# rs485Adaptor.net
KiCad netlist of a schematic drawn in EAGLE
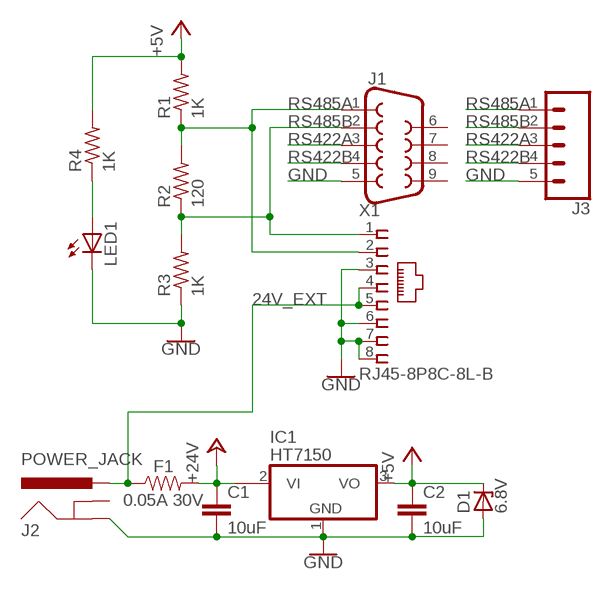
[diagram p0: schematic, sheet 1]

(export (version "E")
  (design (tool "Eeschema 10.0.6"))
  (components
    (comp (ref "C1")
      (value "10uF")
      (footprint "eagle-import:1206")
      (libsource (lib "eagle-import") (part "10UF-1206-6.3V-20%"))
    )
    (comp (ref "C2")
      (value "10uF")
      (footprint "eagle-import:C0805K")
      (libsource (lib "eagle-import") (part "C-EUC0805K"))
    )
    (comp (ref "D1")
      (value "6.8V")
      (footprint "eagle-import:SOD80C")
      (libsource (lib "eagle-import") (part "ZENER-DIODESOD80C"))
    )
    (comp (ref "F1")
      (value "0.05A 30V")
      (footprint "eagle-import:1210")
      (libsource (lib "eagle-import") (part "0.1OHM-1210-1/2W-1%"))
    )
    (comp (ref "IC1")
      (value "HT7150")
      (footprint "eagle-import:SOT89")
      (libsource (lib "eagle-import") (part "MCP1703MB50"))
    )
    (comp (ref "J1")
      (value "DB9FEMALE")
      (footprint "eagle-import:DB9")
      (libsource (lib "eagle-import") (part "DB9FEMALE"))
    )
    (comp (ref "J2")
      (value "POWER_JACK")
      (footprint "eagle-import:POWER_JACK_PTH")
      (libsource (lib "eagle-import") (part "POWER_JACK"))
    )
    (comp (ref "J3")
      (value "CONN_05SCREW")
      (footprint "eagle-import:SCREWTERMINAL-3.5MM-5")
      (libsource (lib "eagle-import") (part "CONN_05SCREW"))
    )
    (comp (ref "LED1")
      (value "LEDCHIP-LED0805")
      (footprint "eagle-import:CHIP-LED0805")
      (libsource (lib "eagle-import") (part "LEDCHIP-LED0805"))
    )
    (comp (ref "R1")
      (value "1K")
      (footprint "eagle-import:R0805")
      (libsource (lib "eagle-import") (part "R-US_R0805"))
    )
    (comp (ref "R2")
      (value "120")
      (footprint "eagle-import:R0805")
      (libsource (lib "eagle-import") (part "R-US_R0805"))
    )
    (comp (ref "R3")
      (value "1K")
      (footprint "eagle-import:R0805")
      (libsource (lib "eagle-import") (part "R-US_R0805"))
    )
    (comp (ref "R4")
      (value "1K")
      (footprint "eagle-import:R0805")
      (libsource (lib "eagle-import") (part "R-US_R0805"))
    )
    (comp (ref "X1")
      (value "RJ45-8P8C-8L-B")
      (footprint "eagle-import:RJ45-SHIELD-DS1128-S80BP")
      (fields (field (name "MF") "TYCO ELECTRONICS") (field (name "MPN") "RJ45-8L-B"))
      (libsource (lib "eagle-import") (part "RJ45-8P8C-8L-B"))
    )
  )
  (nets
    (net (code "1") (name "+5V") (class "Default")
      (node (ref "C2") (pin "1") (pinfunction "1_1") (pintype "passive"))
      (node (ref "D1") (pin "C") (pinfunction "C_C") (pintype "passive"))
      (node (ref "IC1") (pin "3") (pinfunction "VO_3") (pintype "passive"))
      (node (ref "R1") (pin "2") (pinfunction "2_2") (pintype "passive"))
      (node (ref "R4") (pin "2") (pinfunction "2_2") (pintype "passive"))
    )
    (net (code "2") (name "+24V") (class "Default")
      (node (ref "C1") (pin "1") (pinfunction "1_1") (pintype "passive"))
      (node (ref "F1") (pin "2") (pinfunction "2_2") (pintype "passive"))
      (node (ref "IC1") (pin "2@1") (pinfunction "VI1_2@1") (pintype "input"))
    )
    (net (code "3") (name "/24V_EXT") (class "Default")
      (node (ref "F1") (pin "1") (pinfunction "1_1") (pintype "passive"))
      (node (ref "J2") (pin "PWR") (pinfunction "PWR_PWR") (pintype "bidirectional"))
      (node (ref "X1") (pin "4") (pinfunction "4_4") (pintype "passive"))
      (node (ref "X1") (pin "5") (pinfunction "5_5") (pintype "passive"))
    )
    (net (code "4") (name "/RS422A") (class "Default")
      (node (ref "J1") (pin "3") (pinfunction "3_3") (pintype "passive"))
      (node (ref "J3") (pin "3") (pinfunction "3_3") (pintype "passive"))
    )
    (net (code "5") (name "/RS422B") (class "Default")
      (node (ref "J1") (pin "4") (pinfunction "4_4") (pintype "passive"))
      (node (ref "J3") (pin "4") (pinfunction "4_4") (pintype "passive"))
    )
    (net (code "6") (name "/RS485A") (class "Default")
      (node (ref "J1") (pin "1") (pinfunction "1_1") (pintype "passive"))
      (node (ref "J3") (pin "1") (pinfunction "1_1") (pintype "passive"))
      (node (ref "R1") (pin "1") (pinfunction "1_1") (pintype "passive"))
      (node (ref "R2") (pin "2") (pinfunction "2_2") (pintype "passive"))
      (node (ref "X1") (pin "2") (pinfunction "2_2") (pintype "passive"))
    )
    (net (code "7") (name "/RS485B") (class "Default")
      (node (ref "J1") (pin "2") (pinfunction "2_2") (pintype "passive"))
      (node (ref "J3") (pin "2") (pinfunction "2_2") (pintype "passive"))
      (node (ref "R2") (pin "1") (pinfunction "1_1") (pintype "passive"))
      (node (ref "R3") (pin "2") (pinfunction "2_2") (pintype "passive"))
      (node (ref "X1") (pin "1") (pinfunction "1_1") (pintype "passive"))
    )
    (net (code "8") (name "GND") (class "Default")
      (node (ref "C1") (pin "2") (pinfunction "2_2") (pintype "passive"))
      (node (ref "C2") (pin "2") (pinfunction "2_2") (pintype "passive"))
      (node (ref "D1") (pin "A") (pinfunction "A_A") (pintype "passive"))
      (node (ref "IC1") (pin "1") (pinfunction "GND_1") (pintype "passive"))
      (node (ref "J1") (pin "5") (pinfunction "5_5") (pintype "passive"))
      (node (ref "J2") (pin "GND") (pinfunction "GND_GND") (pintype "bidirectional"))
      (node (ref "J3") (pin "5") (pinfunction "5_5") (pintype "passive"))
      (node (ref "LED1") (pin "C") (pinfunction "C_C") (pintype "passive"))
      (node (ref "R3") (pin "1") (pinfunction "1_1") (pintype "passive"))
      (node (ref "X1") (pin "3") (pinfunction "3_3") (pintype "passive"))
      (node (ref "X1") (pin "6") (pinfunction "6_6") (pintype "passive"))
      (node (ref "X1") (pin "7") (pinfunction "7_7") (pintype "passive"))
      (node (ref "X1") (pin "8") (pinfunction "8_8") (pintype "passive"))
    )
    (net (code "9") (name "Net-(LED1-PadA)") (class "Default")
      (node (ref "LED1") (pin "A") (pinfunction "A_A") (pintype "passive"))
      (node (ref "R4") (pin "1") (pinfunction "1_1") (pintype "passive"))
    )
    (net (code "10") (name "unconnected-(IC1-VI-Pad2)") (class "Default")
      (node (ref "IC1") (pin "2") (pinfunction "VI_2") (pintype "input"))
    )
    (net (code "11") (name "unconnected-(J1-Pad6)") (class "Default")
      (node (ref "J1") (pin "6") (pinfunction "6_6") (pintype "passive"))
    )
    (net (code "12") (name "unconnected-(J1-Pad7)") (class "Default")
      (node (ref "J1") (pin "7") (pinfunction "7_7") (pintype "passive"))
    )
    (net (code "13") (name "unconnected-(J1-Pad8)") (class "Default")
      (node (ref "J1") (pin "8") (pinfunction "8_8") (pintype "passive"))
    )
    (net (code "14") (name "unconnected-(J1-Pad9)") (class "Default")
      (node (ref "J1") (pin "9") (pinfunction "9_9") (pintype "passive"))
    )
    (net (code "15") (name "unconnected-(J2-PadGNDBREAK)") (class "Default")
      (node (ref "J2") (pin "GNDBREAK") (pinfunction "GNDBREAK_GNDBREAK") (pintype "bidirectional"))
    )
  )
)
